# V4_HC-05.net
KiCad netlist of a schematic drawn in Altium Designer
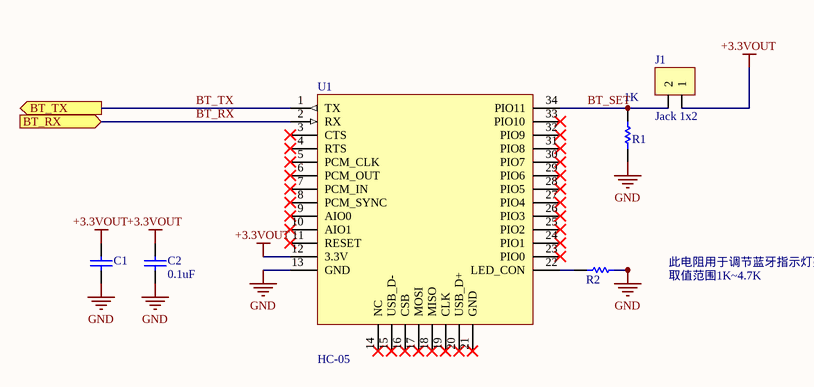
[diagram p0: 海关全向控制器主控板电路V4_HC-05.SchDoc]

(export (version "E")
  (design (tool "Eeschema 10.0.6"))
  (components
    (comp (ref "C1")
      (value "10uF")
      (footprint "C0805")
      (description "CAP")
      (fields (field (name "PUBLISHER") "Altium Limited"))
      (libsource (lib "RLCYDF") (part "CAP"))
    )
    (comp (ref "C2") (value "0.1uF") (footprint "C0805") (libsource (lib "RLCYDF") (part "Cap Semi")))
    (comp (ref "J1")
      (value "Jack 1x2")
      (footprint "A6S-1101-PH")
      (description "插座")
      (libsource (lib "Connector") (part "Jack 1x2"))
    )
    (comp (ref "R1") (value "1K") (footprint "R0805") (libsource (lib "RLCYDF") (part "Res")))
    (comp (ref "R2") (value "1K") (footprint "R0805") (libsource (lib "RLCYDF") (part "Res")))
    (comp (ref "U1") (value "HC-05") (footprint "HC-05") (libsource (lib "Module") (part "HC-05")))
  )
  (nets
    (net (code "1") (name "+3.3VOUT") (class "Default")
      (node (ref "C1") (pin "1") (pinfunction "1_1") (pintype "passive"))
      (node (ref "C2") (pin "2") (pinfunction "2_2") (pintype "passive"))
      (node (ref "J1") (pin "1") (pinfunction "1_1") (pintype "passive"))
      (node (ref "U1") (pin "12") (pinfunction "3.3V_12") (pintype "passive"))
    )
    (net (code "2") (name "/BT_RX") (class "Default")
      (node (ref "U1") (pin "2") (pinfunction "RX_2") (pintype "input"))
    )
    (net (code "3") (name "/BT_SET") (class "Default")
      (node (ref "J1") (pin "2") (pinfunction "2_2") (pintype "passive"))
      (node (ref "R1") (pin "1") (pinfunction "1_1") (pintype "passive"))
      (node (ref "U1") (pin "34") (pinfunction "PIO11_34") (pintype "passive"))
    )
    (net (code "4") (name "/BT_TX") (class "Default")
      (node (ref "U1") (pin "1") (pinfunction "TX_1") (pintype "output"))
    )
    (net (code "5") (name "GND") (class "Default")
      (node (ref "C1") (pin "2") (pinfunction "2_2") (pintype "passive"))
      (node (ref "C2") (pin "1") (pinfunction "1_1") (pintype "passive"))
      (node (ref "R1") (pin "2") (pinfunction "2_2") (pintype "passive"))
      (node (ref "R2") (pin "1") (pinfunction "1_1") (pintype "passive"))
      (node (ref "U1") (pin "13") (pinfunction "GND_13") (pintype "passive"))
    )
    (net (code "6") (name "Net-(U1-LED_CON)") (class "Default")
      (node (ref "R2") (pin "2") (pinfunction "2_2") (pintype "passive"))
      (node (ref "U1") (pin "22") (pinfunction "LED_CON_22") (pintype "passive"))
    )
    (net (code "7") (name "unconnected-(U1-AIO0-Pad9)") (class "Default")
      (node (ref "U1") (pin "9") (pinfunction "AIO0_9") (pintype "passive+no_connect"))
    )
    (net (code "8") (name "unconnected-(U1-AIO1-Pad10)") (class "Default")
      (node (ref "U1") (pin "10") (pinfunction "AIO1_10") (pintype "passive+no_connect"))
    )
    (net (code "9") (name "unconnected-(U1-CLK-Pad19)") (class "Default")
      (node (ref "U1") (pin "19") (pinfunction "CLK_19") (pintype "passive+no_connect"))
    )
    (net (code "10") (name "unconnected-(U1-CSB-Pad16)") (class "Default")
      (node (ref "U1") (pin "16") (pinfunction "CSB_16") (pintype "passive+no_connect"))
    )
    (net (code "11") (name "unconnected-(U1-CTS-Pad3)") (class "Default")
      (node (ref "U1") (pin "3") (pinfunction "CTS_3") (pintype "passive+no_connect"))
    )
    (net (code "12") (name "unconnected-(U1-GND-Pad21)") (class "Default")
      (node (ref "U1") (pin "21") (pinfunction "GND_21") (pintype "passive+no_connect"))
    )
    (net (code "13") (name "unconnected-(U1-MISO-Pad18)") (class "Default")
      (node (ref "U1") (pin "18") (pinfunction "MISO_18") (pintype "passive+no_connect"))
    )
    (net (code "14") (name "unconnected-(U1-MOSI-Pad17)") (class "Default")
      (node (ref "U1") (pin "17") (pinfunction "MOSI_17") (pintype "passive+no_connect"))
    )
    (net (code "15") (name "unconnected-(U1-NC-Pad14)") (class "Default")
      (node (ref "U1") (pin "14") (pinfunction "NC_14") (pintype "passive+no_connect"))
    )
    (net (code "16") (name "unconnected-(U1-PCM_CLK-Pad5)") (class "Default")
      (node (ref "U1") (pin "5") (pinfunction "PCM_CLK_5") (pintype "passive+no_connect"))
    )
    (net (code "17") (name "unconnected-(U1-PCM_IN-Pad7)") (class "Default")
      (node (ref "U1") (pin "7") (pinfunction "PCM_IN_7") (pintype "passive+no_connect"))
    )
    (net (code "18") (name "unconnected-(U1-PCM_OUT-Pad6)") (class "Default")
      (node (ref "U1") (pin "6") (pinfunction "PCM_OUT_6") (pintype "passive+no_connect"))
    )
    (net (code "19") (name "unconnected-(U1-PCM_SYNC-Pad8)") (class "Default")
      (node (ref "U1") (pin "8") (pinfunction "PCM_SYNC_8") (pintype "passive+no_connect"))
    )
    (net (code "20") (name "unconnected-(U1-PIO0-Pad23)") (class "Default")
      (node (ref "U1") (pin "23") (pinfunction "PIO0_23") (pintype "passive+no_connect"))
    )
    (net (code "21") (name "unconnected-(U1-PIO1-Pad24)") (class "Default")
      (node (ref "U1") (pin "24") (pinfunction "PIO1_24") (pintype "passive+no_connect"))
    )
    (net (code "22") (name "unconnected-(U1-PIO2-Pad25)") (class "Default")
      (node (ref "U1") (pin "25") (pinfunction "PIO2_25") (pintype "passive+no_connect"))
    )
    (net (code "23") (name "unconnected-(U1-PIO3-Pad26)") (class "Default")
      (node (ref "U1") (pin "26") (pinfunction "PIO3_26") (pintype "passive+no_connect"))
    )
    (net (code "24") (name "unconnected-(U1-PIO4-Pad27)") (class "Default")
      (node (ref "U1") (pin "27") (pinfunction "PIO4_27") (pintype "passive+no_connect"))
    )
    (net (code "25") (name "unconnected-(U1-PIO5-Pad28)") (class "Default")
      (node (ref "U1") (pin "28") (pinfunction "PIO5_28") (pintype "passive+no_connect"))
    )
    (net (code "26") (name "unconnected-(U1-PIO6-Pad29)") (class "Default")
      (node (ref "U1") (pin "29") (pinfunction "PIO6_29") (pintype "passive+no_connect"))
    )
    (net (code "27") (name "unconnected-(U1-PIO7-Pad30)") (class "Default")
      (node (ref "U1") (pin "30") (pinfunction "PIO7_30") (pintype "passive+no_connect"))
    )
    (net (code "28") (name "unconnected-(U1-PIO8-Pad31)") (class "Default")
      (node (ref "U1") (pin "31") (pinfunction "PIO8_31") (pintype "passive+no_connect"))
    )
    (net (code "29") (name "unconnected-(U1-PIO9-Pad32)") (class "Default")
      (node (ref "U1") (pin "32") (pinfunction "PIO9_32") (pintype "passive+no_connect"))
    )
    (net (code "30") (name "unconnected-(U1-PIO10-Pad33)") (class "Default")
      (node (ref "U1") (pin "33") (pinfunction "PIO10_33") (pintype "passive+no_connect"))
    )
    (net (code "31") (name "unconnected-(U1-RESET-Pad11)") (class "Default")
      (node (ref "U1") (pin "11") (pinfunction "RESET_11") (pintype "passive+no_connect"))
    )
    (net (code "32") (name "unconnected-(U1-RTS-Pad4)") (class "Default")
      (node (ref "U1") (pin "4") (pinfunction "RTS_4") (pintype "passive+no_connect"))
    )
    (net (code "33") (name "unconnected-(U1-USB_D+-Pad20)") (class "Default")
      (node (ref "U1") (pin "20") (pinfunction "USB_D+_20") (pintype "passive+no_connect"))
    )
    (net (code "34") (name "unconnected-(U1-USB_D--Pad15)") (class "Default")
      (node (ref "U1") (pin "15") (pinfunction "USB_D-_15") (pintype "passive+no_connect"))
    )
  )
)
